# eiffel_mini_Version2_2.net
KiCad netlist of a schematic drawn in EAGLE
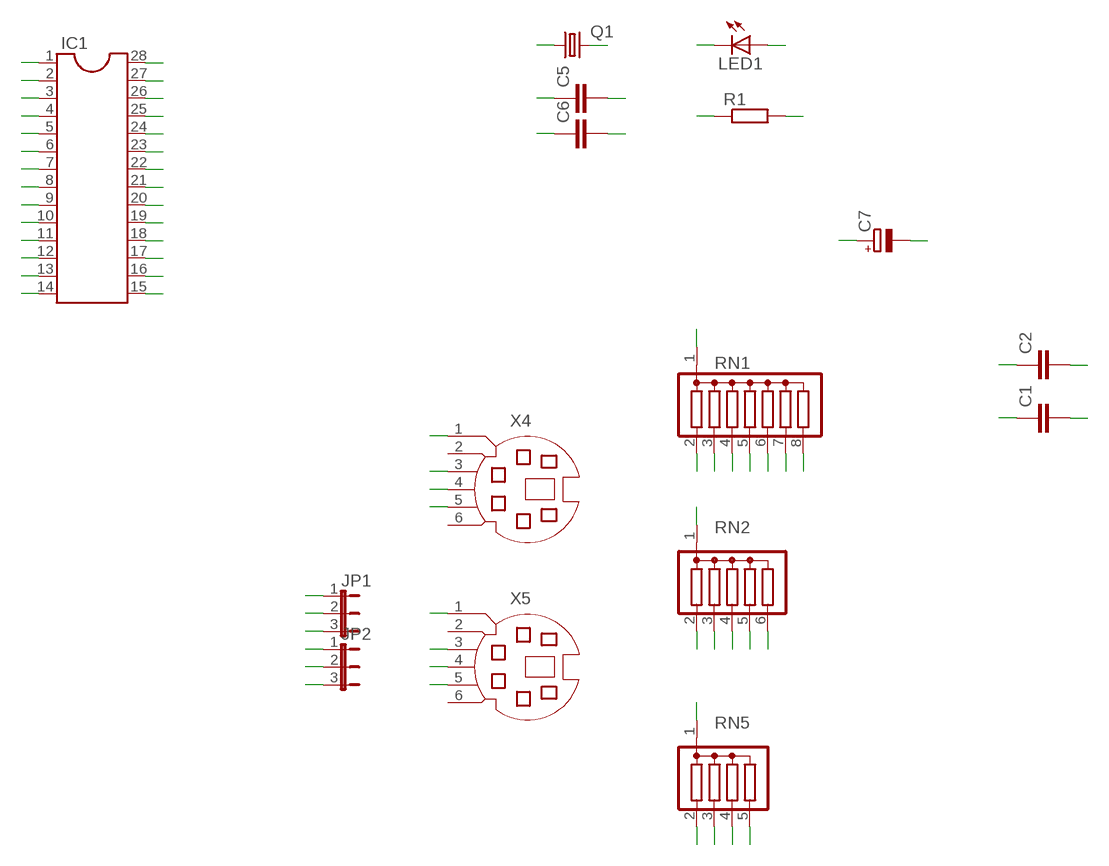
[diagram p0: schematic, sheet 1]

(export (version "E")
  (design (tool "Eeschema 10.0.6"))
  (components
    (comp (ref "C1")
      (value "C-EU025-060X050")
      (footprint "eagle-import:C025-060X050")
      (libsource (lib "eagle-import") (part "C-EU025-060X050"))
    )
    (comp (ref "C2")
      (value "C-EU025-060X050")
      (footprint "eagle-import:C025-060X050")
      (libsource (lib "eagle-import") (part "C-EU025-060X050"))
    )
    (comp (ref "C5")
      (value "C-EU025-024X044")
      (footprint "eagle-import:C025-024X044")
      (libsource (lib "eagle-import") (part "C-EU025-024X044"))
    )
    (comp (ref "C6")
      (value "C-EU025-024X044")
      (footprint "eagle-import:C025-024X044")
      (libsource (lib "eagle-import") (part "C-EU025-024X044"))
    )
    (comp (ref "C7")
      (value "CPOL-EUE2,5-6E")
      (footprint "eagle-import:E2,5-6E")
      (libsource (lib "eagle-import") (part "CPOL-EUE2,5-6E"))
    )
    (comp (ref "IC1")
      (value "DIL28-3")
      (footprint "eagle-import:DIL28-3")
      (libsource (lib "eagle-import") (part "DIL28-3"))
    )
    (comp (ref "JP1")
      (value "JP2E")
      (footprint "eagle-import:JP2")
      (libsource (lib "eagle-import") (part "JP2E"))
    )
    (comp (ref "JP2")
      (value "JP2E")
      (footprint "eagle-import:JP2")
      (libsource (lib "eagle-import") (part "JP2E"))
    )
    (comp (ref "LED1")
      (value "LED3MM")
      (footprint "eagle-import:LED3MM")
      (libsource (lib "eagle-import") (part "LED3MM"))
    )
    (comp (ref "Q1")
      (value "CRYSTALHC49S")
      (footprint "eagle-import:HC49_S")
      (libsource (lib "eagle-import") (part "CRYSTALHC49S"))
    )
    (comp (ref "R1")
      (value "R-EU_0204/7")
      (footprint "eagle-import:0204_7")
      (libsource (lib "eagle-import") (part "R-EU_0204/7"))
    )
    (comp (ref "RN1")
      (value "G07R")
      (footprint "eagle-import:SIL8")
      (libsource (lib "eagle-import") (part "G07R"))
    )
    (comp (ref "RN2")
      (value "G05R")
      (footprint "eagle-import:SIL6")
      (libsource (lib "eagle-import") (part "G05R"))
    )
    (comp (ref "RN5")
      (value "G04R")
      (footprint "eagle-import:SIL5")
      (libsource (lib "eagle-import") (part "G04R"))
    )
    (comp (ref "X4")
      (value "MD06S")
      (footprint "eagle-import:MDIN06S")
      (libsource (lib "eagle-import") (part "MD06S"))
    )
    (comp (ref "X5")
      (value "MD06S")
      (footprint "eagle-import:MDIN06S")
      (libsource (lib "eagle-import") (part "MD06S"))
    )
  )
  (nets
    (net (code "1") (name "/GND") (class "Default")
      (node (ref "C1") (pin "2") (pinfunction "2_2") (pintype "passive"))
      (node (ref "C2") (pin "2") (pinfunction "2_2") (pintype "passive"))
      (node (ref "C5") (pin "2") (pinfunction "2_2") (pintype "passive"))
      (node (ref "C6") (pin "2") (pinfunction "2_2") (pintype "passive"))
      (node (ref "C7") (pin "-") (pinfunction "-_-") (pintype "passive"))
      (node (ref "IC1") (pin "19") (pinfunction "19_19") (pintype "passive"))
      (node (ref "IC1") (pin "8") (pinfunction "8_8") (pintype "passive"))
      (node (ref "JP2") (pin "2") (pinfunction "2_2") (pintype "passive"))
      (node (ref "JP2") (pin "3") (pinfunction "3_3") (pintype "passive"))
      (node (ref "LED1") (pin "K") (pinfunction "C_K") (pintype "passive"))
      (node (ref "X4") (pin "3") (pinfunction "3_3") (pintype "passive"))
      (node (ref "X5") (pin "3") (pinfunction "3_3") (pintype "passive"))
    )
    (net (code "2") (name "/LED") (class "Default")
      (node (ref "LED1") (pin "A") (pinfunction "A_A") (pintype "passive"))
      (node (ref "R1") (pin "1") (pinfunction "1_1") (pintype "passive"))
    )
    (net (code "3") (name "/RA0") (class "Default")
      (node (ref "IC1") (pin "2") (pinfunction "2_2") (pintype "passive"))
      (node (ref "RN1") (pin "8") (pinfunction "8_8") (pintype "passive"))
    )
    (net (code "4") (name "/RA1") (class "Default")
      (node (ref "IC1") (pin "3") (pinfunction "3_3") (pintype "passive"))
      (node (ref "RN1") (pin "2") (pinfunction "2_2") (pintype "passive"))
    )
    (net (code "5") (name "/RA2") (class "Default")
      (node (ref "IC1") (pin "4") (pinfunction "4_4") (pintype "passive"))
      (node (ref "RN1") (pin "3") (pinfunction "3_3") (pintype "passive"))
    )
    (net (code "6") (name "/RA3") (class "Default")
      (node (ref "IC1") (pin "5") (pinfunction "5_5") (pintype "passive"))
      (node (ref "RN1") (pin "4") (pinfunction "4_4") (pintype "passive"))
    )
    (net (code "7") (name "/RA4") (class "Default")
      (node (ref "IC1") (pin "6") (pinfunction "6_6") (pintype "passive"))
      (node (ref "RN1") (pin "5") (pinfunction "5_5") (pintype "passive"))
    )
    (net (code "8") (name "/RA5") (class "Default")
      (node (ref "IC1") (pin "7") (pinfunction "7_7") (pintype "passive"))
      (node (ref "RN1") (pin "6") (pinfunction "6_6") (pintype "passive"))
    )
    (net (code "9") (name "/RB0") (class "Default")
      (node (ref "IC1") (pin "21") (pinfunction "21_21") (pintype "passive"))
      (node (ref "RN5") (pin "2") (pinfunction "2_2") (pintype "passive"))
      (node (ref "X5") (pin "1") (pinfunction "1_1") (pintype "passive"))
    )
    (net (code "10") (name "/RB1") (class "Default")
      (node (ref "IC1") (pin "22") (pinfunction "22_22") (pintype "passive"))
      (node (ref "RN5") (pin "3") (pinfunction "3_3") (pintype "passive"))
      (node (ref "X5") (pin "5") (pinfunction "5_5") (pintype "passive"))
    )
    (net (code "11") (name "/RB2") (class "Default")
      (node (ref "IC1") (pin "23") (pinfunction "23_23") (pintype "passive"))
      (node (ref "RN5") (pin "4") (pinfunction "4_4") (pintype "passive"))
      (node (ref "X4") (pin "1") (pinfunction "1_1") (pintype "passive"))
    )
    (net (code "12") (name "/RB3") (class "Default")
      (node (ref "IC1") (pin "24") (pinfunction "24_24") (pintype "passive"))
      (node (ref "RN5") (pin "5") (pinfunction "5_5") (pintype "passive"))
      (node (ref "X4") (pin "5") (pinfunction "5_5") (pintype "passive"))
    )
    (net (code "13") (name "/RC0") (class "Default")
      (node (ref "IC1") (pin "11") (pinfunction "11_11") (pintype "passive"))
      (node (ref "RN2") (pin "2") (pinfunction "2_2") (pintype "passive"))
    )
    (net (code "14") (name "/RC1") (class "Default")
      (node (ref "IC1") (pin "12") (pinfunction "12_12") (pintype "passive"))
      (node (ref "RN2") (pin "3") (pinfunction "3_3") (pintype "passive"))
    )
    (net (code "15") (name "/RC2") (class "Default")
      (node (ref "IC1") (pin "13") (pinfunction "13_13") (pintype "passive"))
      (node (ref "RN2") (pin "4") (pinfunction "4_4") (pintype "passive"))
    )
    (net (code "16") (name "/RC3") (class "Default")
      (node (ref "IC1") (pin "14") (pinfunction "14_14") (pintype "passive"))
      (node (ref "RN2") (pin "5") (pinfunction "5_5") (pintype "passive"))
    )
    (net (code "17") (name "/RC4") (class "Default")
      (node (ref "IC1") (pin "15") (pinfunction "15_15") (pintype "passive"))
      (node (ref "RN2") (pin "6") (pinfunction "6_6") (pintype "passive"))
    )
    (net (code "18") (name "/RC6") (class "Default")
      (node (ref "IC1") (pin "17") (pinfunction "17_17") (pintype "passive"))
      (node (ref "JP2") (pin "1") (pinfunction "1_1") (pintype "passive"))
    )
    (net (code "19") (name "/RC7") (class "Default")
      (node (ref "IC1") (pin "18") (pinfunction "18_18") (pintype "passive"))
      (node (ref "JP1") (pin "3") (pinfunction "3_3") (pintype "passive"))
    )
    (net (code "20") (name "/VCC") (class "Default")
      (node (ref "C1") (pin "1") (pinfunction "1_1") (pintype "passive"))
      (node (ref "C2") (pin "1") (pinfunction "1_1") (pintype "passive"))
      (node (ref "C7") (pin "+") (pinfunction "+_+") (pintype "passive"))
      (node (ref "IC1") (pin "20") (pinfunction "20_20") (pintype "passive"))
      (node (ref "JP1") (pin "1") (pinfunction "1_1") (pintype "passive"))
      (node (ref "JP1") (pin "2") (pinfunction "2_2") (pintype "passive"))
      (node (ref "R1") (pin "2") (pinfunction "2_2") (pintype "passive"))
      (node (ref "RN1") (pin "1") (pinfunction "1_1") (pintype "passive"))
      (node (ref "RN2") (pin "1") (pinfunction "1_1") (pintype "passive"))
      (node (ref "RN5") (pin "1") (pinfunction "1_1") (pintype "passive"))
      (node (ref "X4") (pin "4") (pinfunction "4_4") (pintype "passive"))
      (node (ref "X5") (pin "4") (pinfunction "4_4") (pintype "passive"))
    )
    (net (code "21") (name "/XI") (class "Default")
      (node (ref "C5") (pin "1") (pinfunction "1_1") (pintype "passive"))
      (node (ref "IC1") (pin "9") (pinfunction "9_9") (pintype "passive"))
      (node (ref "Q1") (pin "1") (pinfunction "1_1") (pintype "passive"))
    )
    (net (code "22") (name "/XO") (class "Default")
      (node (ref "C6") (pin "1") (pinfunction "1_1") (pintype "passive"))
      (node (ref "IC1") (pin "10") (pinfunction "10_10") (pintype "passive"))
      (node (ref "Q1") (pin "2") (pinfunction "2_2") (pintype "passive"))
    )
    (net (code "23") (name "/{slash}MCLR") (class "Default")
      (node (ref "IC1") (pin "1") (pinfunction "1_1") (pintype "passive"))
      (node (ref "RN1") (pin "7") (pinfunction "7_7") (pintype "passive"))
    )
    (net (code "24") (name "unconnected-(IC1-Pad16)") (class "Default")
      (node (ref "IC1") (pin "16") (pinfunction "16_16") (pintype "passive"))
    )
    (net (code "25") (name "unconnected-(IC1-Pad25)") (class "Default")
      (node (ref "IC1") (pin "25") (pinfunction "25_25") (pintype "passive"))
    )
    (net (code "26") (name "unconnected-(IC1-Pad26)") (class "Default")
      (node (ref "IC1") (pin "26") (pinfunction "26_26") (pintype "passive"))
    )
    (net (code "27") (name "unconnected-(IC1-Pad27)") (class "Default")
      (node (ref "IC1") (pin "27") (pinfunction "27_27") (pintype "passive"))
    )
    (net (code "28") (name "unconnected-(IC1-Pad28)") (class "Default")
      (node (ref "IC1") (pin "28") (pinfunction "28_28") (pintype "passive"))
    )
    (net (code "29") (name "unconnected-(X4-Pad2)") (class "Default")
      (node (ref "X4") (pin "2") (pinfunction "2_2") (pintype "passive"))
    )
    (net (code "30") (name "unconnected-(X4-Pad6)") (class "Default")
      (node (ref "X4") (pin "6") (pinfunction "6_6") (pintype "passive"))
    )
    (net (code "31") (name "unconnected-(X5-Pad2)") (class "Default")
      (node (ref "X5") (pin "2") (pinfunction "2_2") (pintype "passive"))
    )
    (net (code "32") (name "unconnected-(X5-Pad6)") (class "Default")
      (node (ref "X5") (pin "6") (pinfunction "6_6") (pintype "passive"))
    )
  )
)
